# Hermit_Board_Rev_A5.net
KiCad netlist of a schematic drawn in EAGLE
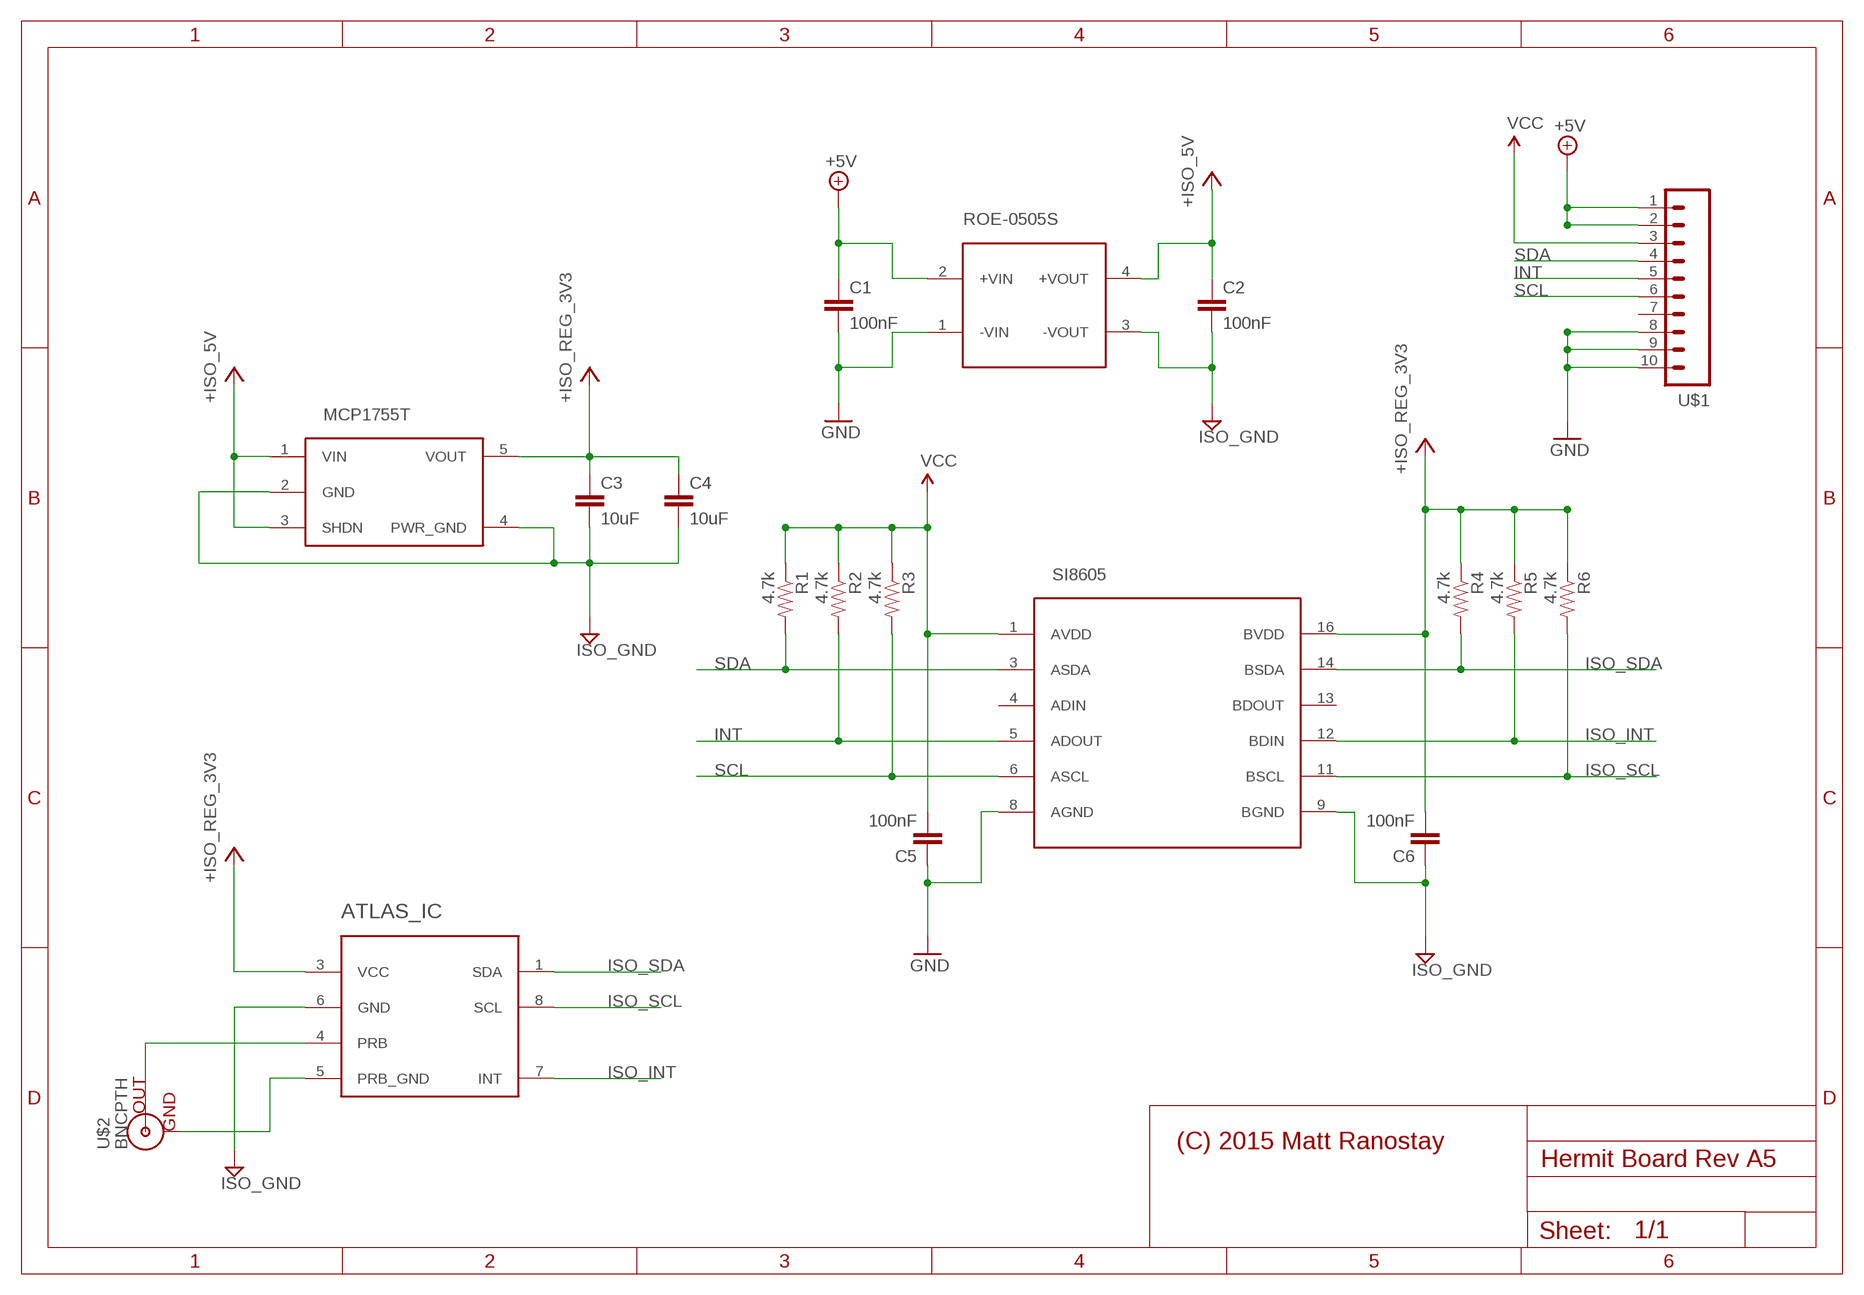
[diagram p0: schematic, sheet 1]

(export (version "E")
  (design (tool "Eeschema 10.0.6"))
  (components
    (comp (ref "ATLAS_IC")
      (value "ATLAS-OEM")
      (footprint "eagle-import:ATLAS-OEM")
      (libsource (lib "eagle-import") (part "ATLAS-OEM"))
    )
    (comp (ref "C1")
      (value "100nF")
      (footprint "eagle-import:0805")
      (libsource (lib "eagle-import") (part "CAP0805"))
    )
    (comp (ref "C2")
      (value "100nF")
      (footprint "eagle-import:0805")
      (libsource (lib "eagle-import") (part "CAP0805"))
    )
    (comp (ref "C3")
      (value "10uF")
      (footprint "eagle-import:0805")
      (libsource (lib "eagle-import") (part "CAP0805"))
    )
    (comp (ref "C4")
      (value "10uF")
      (footprint "eagle-import:0805")
      (libsource (lib "eagle-import") (part "CAP0805"))
    )
    (comp (ref "C5")
      (value "100nF")
      (footprint "eagle-import:0805")
      (libsource (lib "eagle-import") (part "CAP0805"))
    )
    (comp (ref "C6")
      (value "100nF")
      (footprint "eagle-import:0805")
      (libsource (lib "eagle-import") (part "CAP0805"))
    )
    (comp (ref "MCP1755T")
      (value "MCP1755T")
      (footprint "eagle-import:SOT-23-5")
      (libsource (lib "eagle-import") (part "MCP1755T"))
    )
    (comp (ref "R1")
      (value "4.7k")
      (footprint "eagle-import:0805")
      (libsource (lib "eagle-import") (part "RESISTOR0805-RES"))
    )
    (comp (ref "R2")
      (value "4.7k")
      (footprint "eagle-import:0805")
      (libsource (lib "eagle-import") (part "RESISTOR0805-RES"))
    )
    (comp (ref "R3")
      (value "4.7k")
      (footprint "eagle-import:0805")
      (libsource (lib "eagle-import") (part "RESISTOR0805-RES"))
    )
    (comp (ref "R4")
      (value "4.7k")
      (footprint "eagle-import:0805")
      (libsource (lib "eagle-import") (part "RESISTOR0805-RES"))
    )
    (comp (ref "R5")
      (value "4.7k")
      (footprint "eagle-import:0805")
      (libsource (lib "eagle-import") (part "RESISTOR0805-RES"))
    )
    (comp (ref "R6")
      (value "4.7k")
      (footprint "eagle-import:0805")
      (libsource (lib "eagle-import") (part "RESISTOR0805-RES"))
    )
    (comp (ref "ROE-0505S")
      (value "ROE-0505S")
      (footprint "eagle-import:SIP4")
      (libsource (lib "eagle-import") (part "ROE-0505S"))
    )
    (comp (ref "SI8605")
      (value "SI8605")
      (footprint "eagle-import:SOIC16-1.27-10X3.9MM")
      (libsource (lib "eagle-import") (part "SI8605"))
    )
    (comp (ref "U$1")
      (value "M10SILK_FEMALE_PTH")
      (footprint "eagle-import:1X10")
      (libsource (lib "eagle-import") (part "M10SILK_FEMALE_PTH"))
    )
    (comp (ref "U$2")
      (value "BNCPTH")
      (footprint "eagle-import:BNC")
      (libsource (lib "eagle-import") (part "BNCPTH"))
    )
  )
  (nets
    (net (code "1") (name "+5V") (class "Default")
      (node (ref "C1") (pin "1") (pinfunction "1_1") (pintype "passive"))
      (node (ref "ROE-0505S") (pin "2") (pinfunction "+VIN_2") (pintype "power_in"))
      (node (ref "U$1") (pin "1") (pinfunction "1_1") (pintype "passive"))
      (node (ref "U$1") (pin "2") (pinfunction "2_2") (pintype "passive"))
    )
    (net (code "2") (name "+ISO_5V") (class "Default")
      (node (ref "C2") (pin "1") (pinfunction "1_1") (pintype "passive"))
      (node (ref "MCP1755T") (pin "1") (pinfunction "VIN_1") (pintype "power_in"))
      (node (ref "MCP1755T") (pin "3") (pinfunction "SHDN_3") (pintype "input"))
      (node (ref "ROE-0505S") (pin "4") (pinfunction "+VOUT_4") (pintype "power_in"))
    )
    (net (code "3") (name "+ISO_REG_3V3") (class "Default")
      (node (ref "ATLAS_IC") (pin "3") (pinfunction "VCC_3") (pintype "power_in"))
      (node (ref "C3") (pin "1") (pinfunction "1_1") (pintype "passive"))
      (node (ref "C4") (pin "1") (pinfunction "1_1") (pintype "passive"))
      (node (ref "C6") (pin "2") (pinfunction "2_2") (pintype "passive"))
      (node (ref "MCP1755T") (pin "5") (pinfunction "VOUT_5") (pintype "power_in"))
      (node (ref "R4") (pin "1") (pinfunction "1_1") (pintype "passive"))
      (node (ref "R5") (pin "1") (pinfunction "1_1") (pintype "passive"))
      (node (ref "R6") (pin "1") (pinfunction "1_1") (pintype "passive"))
      (node (ref "SI8605") (pin "16") (pinfunction "BVDD_16") (pintype "power_in"))
    )
    (net (code "4") (name "/INT") (class "Default")
      (node (ref "R2") (pin "2") (pinfunction "2_2") (pintype "passive"))
      (node (ref "SI8605") (pin "5") (pinfunction "ADOUT_5") (pintype "output"))
      (node (ref "U$1") (pin "5") (pinfunction "5_5") (pintype "passive"))
    )
    (net (code "5") (name "/ISO_INT") (class "Default")
      (node (ref "ATLAS_IC") (pin "7") (pinfunction "INT_7") (pintype "output"))
      (node (ref "R5") (pin "2") (pinfunction "2_2") (pintype "passive"))
      (node (ref "SI8605") (pin "12") (pinfunction "BDIN_12") (pintype "input"))
    )
    (net (code "6") (name "/ISO_SCL") (class "Default")
      (node (ref "ATLAS_IC") (pin "8") (pinfunction "SCL_8") (pintype "bidirectional"))
      (node (ref "R6") (pin "2") (pinfunction "2_2") (pintype "passive"))
      (node (ref "SI8605") (pin "11") (pinfunction "BSCL_11") (pintype "bidirectional"))
    )
    (net (code "7") (name "/ISO_SDA") (class "Default")
      (node (ref "ATLAS_IC") (pin "1") (pinfunction "SDA_1") (pintype "bidirectional"))
      (node (ref "R4") (pin "2") (pinfunction "2_2") (pintype "passive"))
      (node (ref "SI8605") (pin "14") (pinfunction "BSDA_14") (pintype "bidirectional"))
    )
    (net (code "8") (name "/SCL") (class "Default")
      (node (ref "R3") (pin "2") (pinfunction "2_2") (pintype "passive"))
      (node (ref "SI8605") (pin "6") (pinfunction "ASCL_6") (pintype "bidirectional"))
      (node (ref "U$1") (pin "6") (pinfunction "6_6") (pintype "passive"))
    )
    (net (code "9") (name "/SDA") (class "Default")
      (node (ref "R1") (pin "2") (pinfunction "2_2") (pintype "passive"))
      (node (ref "SI8605") (pin "3") (pinfunction "ASDA_3") (pintype "bidirectional"))
      (node (ref "U$1") (pin "4") (pinfunction "4_4") (pintype "passive"))
    )
    (net (code "10") (name "GND") (class "Default")
      (node (ref "C1") (pin "2") (pinfunction "2_2") (pintype "passive"))
      (node (ref "C5") (pin "1") (pinfunction "1_1") (pintype "passive"))
      (node (ref "ROE-0505S") (pin "1") (pinfunction "-VIN_1") (pintype "power_in"))
      (node (ref "SI8605") (pin "8") (pinfunction "AGND_8") (pintype "power_in"))
      (node (ref "U$1") (pin "10") (pinfunction "10_10") (pintype "passive"))
      (node (ref "U$1") (pin "8") (pinfunction "8_8") (pintype "passive"))
      (node (ref "U$1") (pin "9") (pinfunction "9_9") (pintype "passive"))
    )
    (net (code "11") (name "ISO_GND") (class "Default")
      (node (ref "ATLAS_IC") (pin "6") (pinfunction "GND_6") (pintype "power_in"))
      (node (ref "C2") (pin "2") (pinfunction "2_2") (pintype "passive"))
      (node (ref "C3") (pin "2") (pinfunction "2_2") (pintype "passive"))
      (node (ref "C4") (pin "2") (pinfunction "2_2") (pintype "passive"))
      (node (ref "C6") (pin "1") (pinfunction "1_1") (pintype "passive"))
      (node (ref "MCP1755T") (pin "2") (pinfunction "GND_2") (pintype "power_in"))
      (node (ref "MCP1755T") (pin "4") (pinfunction "PWR_GND_4") (pintype "power_in"))
      (node (ref "ROE-0505S") (pin "3") (pinfunction "-VOUT_3") (pintype "power_in"))
      (node (ref "SI8605") (pin "9") (pinfunction "BGND_9") (pintype "power_in"))
    )
    (net (code "12") (name "Net-(ATLAS_IC-PRB)") (class "Default")
      (node (ref "ATLAS_IC") (pin "4") (pinfunction "PRB_4") (pintype "input"))
      (node (ref "U$2") (pin "S") (pinfunction "OUT_S") (pintype "bidirectional"))
    )
    (net (code "13") (name "Net-(ATLAS_IC-PRB_GND)") (class "Default")
      (node (ref "ATLAS_IC") (pin "5") (pinfunction "PRB_GND_5") (pintype "power_in"))
      (node (ref "U$2") (pin "GND") (pinfunction "GND_GND") (pintype "bidirectional"))
    )
    (net (code "14") (name "VCC") (class "Default")
      (node (ref "C5") (pin "2") (pinfunction "2_2") (pintype "passive"))
      (node (ref "R1") (pin "1") (pinfunction "1_1") (pintype "passive"))
      (node (ref "R2") (pin "1") (pinfunction "1_1") (pintype "passive"))
      (node (ref "R3") (pin "1") (pinfunction "1_1") (pintype "passive"))
      (node (ref "SI8605") (pin "1") (pinfunction "AVDD_1") (pintype "power_in"))
      (node (ref "U$1") (pin "3") (pinfunction "3_3") (pintype "passive"))
    )
    (net (code "15") (name "unconnected-(SI8605-ADIN-Pad4)") (class "Default")
      (node (ref "SI8605") (pin "4") (pinfunction "ADIN_4") (pintype "input"))
    )
    (net (code "16") (name "unconnected-(SI8605-BDOUT-Pad13)") (class "Default")
      (node (ref "SI8605") (pin "13") (pinfunction "BDOUT_13") (pintype "output"))
    )
    (net (code "17") (name "unconnected-(U$1-Pad7)") (class "Default")
      (node (ref "U$1") (pin "7") (pinfunction "7_7") (pintype "passive"))
    )
  )
)
